# gitarukuranjadi.net
KiCad netlist of a schematic drawn in Altium Designer
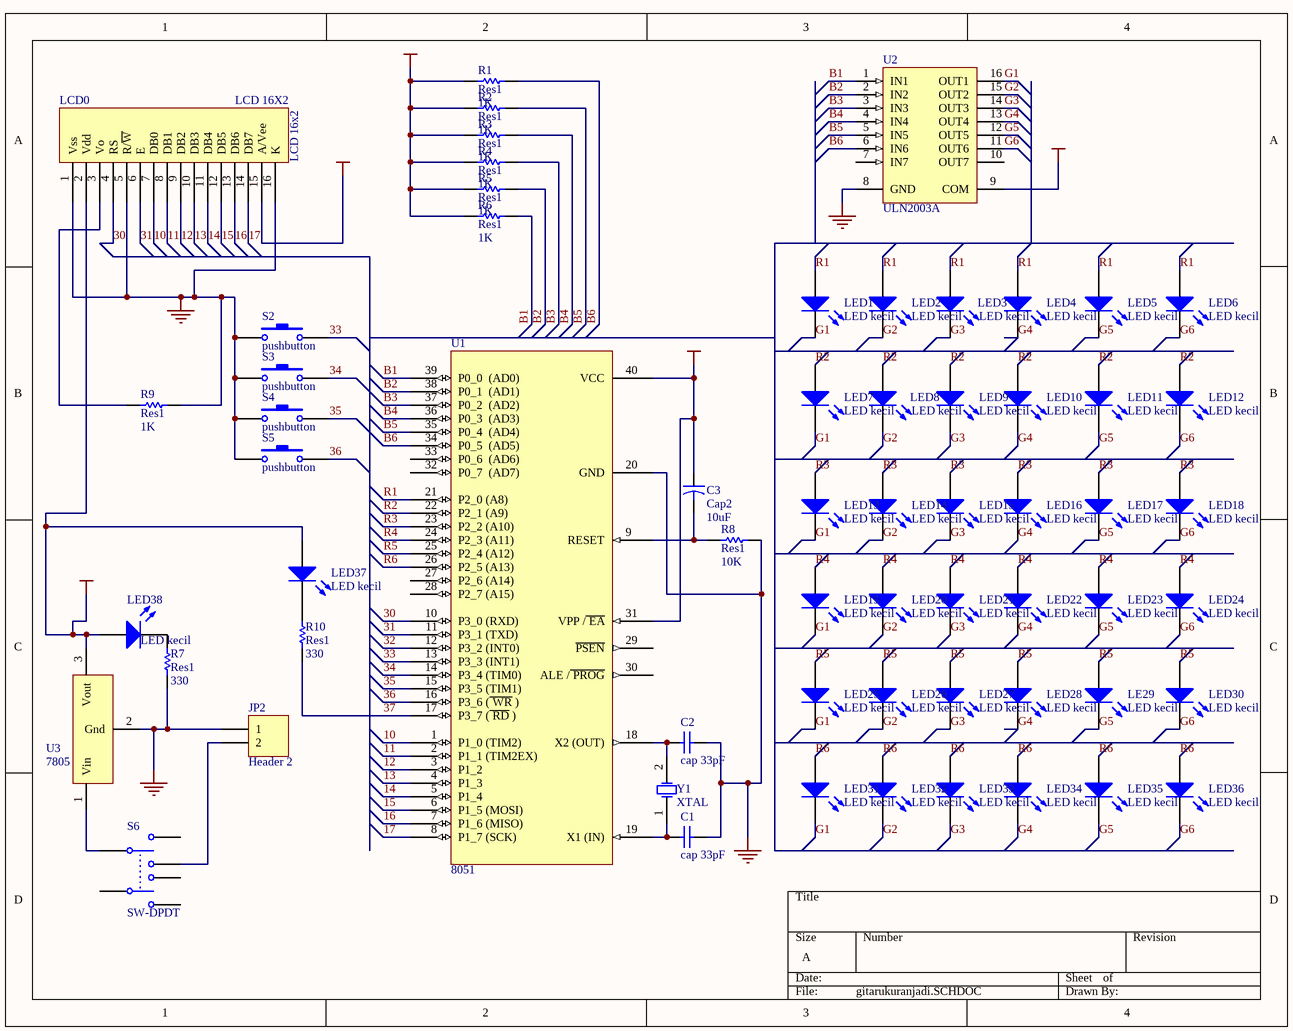
[diagram p0: gitarukuranjadi.SCHDOC]

(export (version "E")
  (design (tool "Eeschema 10.0.6"))
  (components
    (comp (ref "C1")
      (value "cap 33pF")
      (footprint "cap 22/33uF")
      (libsource (lib "agfa other components") (part "cap 22/33uF"))
    )
    (comp (ref "C2")
      (value "cap 33pF")
      (footprint "cap 22/33uF")
      (libsource (lib "agfa other components") (part "cap 22/33uF"))
    )
    (comp (ref "C3")
      (value "Cap2")
      (footprint "CAPR5-4X5")
      (description "Capacitor")
      (fields (field (name "ALTIUM_VALUE") "10uF") (field (name "PUBLISHER") "Altium Limited"))
      (libsource (lib "Miscellaneous Devices") (part "Cap2"))
    )
    (comp (ref "JP2")
      (value "Header 2")
      (footprint "HDR1X2")
      (description "Header, 2-Pin")
      (fields (field (name "PUBLISHER") "Altium Limited"))
      (libsource (lib "Miscellaneous Connectors") (part "Header 2"))
    )
    (comp (ref "LCD0")
      (value "LCD 16X2")
      (footprint "LCD 16X2")
      (libsource (lib "agfa other components") (part "LCD 16X2"))
    )
    (comp (ref "LE29")
      (value "LED kecil")
      (footprint "LED kecil")
      (libsource (lib "agfa other components") (part "LED kecil"))
    )
    (comp (ref "LED1")
      (value "LED kecil")
      (footprint "LED kecil")
      (libsource (lib "agfa other components") (part "LED kecil"))
    )
    (comp (ref "LED2")
      (value "LED kecil")
      (footprint "LED kecil")
      (libsource (lib "agfa other components") (part "LED kecil"))
    )
    (comp (ref "LED3")
      (value "LED kecil")
      (footprint "LED kecil")
      (libsource (lib "agfa other components") (part "LED kecil"))
    )
    (comp (ref "LED4")
      (value "LED kecil")
      (footprint "LED kecil")
      (libsource (lib "agfa other components") (part "LED kecil"))
    )
    (comp (ref "LED5")
      (value "LED kecil")
      (footprint "LED kecil")
      (libsource (lib "agfa other components") (part "LED kecil"))
    )
    (comp (ref "LED6")
      (value "LED kecil")
      (footprint "LED kecil")
      (libsource (lib "agfa other components") (part "LED kecil"))
    )
    (comp (ref "LED7")
      (value "LED kecil")
      (footprint "LED kecil")
      (libsource (lib "agfa other components") (part "LED kecil"))
    )
    (comp (ref "LED8")
      (value "LED kecil")
      (footprint "LED kecil")
      (libsource (lib "agfa other components") (part "LED kecil"))
    )
    (comp (ref "LED9")
      (value "LED kecil")
      (footprint "LED kecil")
      (libsource (lib "agfa other components") (part "LED kecil"))
    )
    (comp (ref "LED10")
      (value "LED kecil")
      (footprint "LED kecil")
      (libsource (lib "agfa other components") (part "LED kecil"))
    )
    (comp (ref "LED11")
      (value "LED kecil")
      (footprint "LED kecil")
      (libsource (lib "agfa other components") (part "LED kecil"))
    )
    (comp (ref "LED12")
      (value "LED kecil")
      (footprint "LED kecil")
      (libsource (lib "agfa other components") (part "LED kecil"))
    )
    (comp (ref "LED13")
      (value "LED kecil")
      (footprint "LED kecil")
      (libsource (lib "agfa other components") (part "LED kecil"))
    )
    (comp (ref "LED14")
      (value "LED kecil")
      (footprint "LED kecil")
      (libsource (lib "agfa other components") (part "LED kecil"))
    )
    (comp (ref "LED15")
      (value "LED kecil")
      (footprint "LED kecil")
      (libsource (lib "agfa other components") (part "LED kecil"))
    )
    (comp (ref "LED16")
      (value "LED kecil")
      (footprint "LED kecil")
      (libsource (lib "agfa other components") (part "LED kecil"))
    )
    (comp (ref "LED17")
      (value "LED kecil")
      (footprint "LED kecil")
      (libsource (lib "agfa other components") (part "LED kecil"))
    )
    (comp (ref "LED18")
      (value "LED kecil")
      (footprint "LED kecil")
      (libsource (lib "agfa other components") (part "LED kecil"))
    )
    (comp (ref "LED19")
      (value "LED kecil")
      (footprint "LED kecil")
      (libsource (lib "agfa other components") (part "LED kecil"))
    )
    (comp (ref "LED20")
      (value "LED kecil")
      (footprint "LED kecil")
      (libsource (lib "agfa other components") (part "LED kecil"))
    )
    (comp (ref "LED21")
      (value "LED kecil")
      (footprint "LED kecil")
      (libsource (lib "agfa other components") (part "LED kecil"))
    )
    (comp (ref "LED22")
      (value "LED kecil")
      (footprint "LED kecil")
      (libsource (lib "agfa other components") (part "LED kecil"))
    )
    (comp (ref "LED23")
      (value "LED kecil")
      (footprint "LED kecil")
      (libsource (lib "agfa other components") (part "LED kecil"))
    )
    (comp (ref "LED24")
      (value "LED kecil")
      (footprint "LED kecil")
      (libsource (lib "agfa other components") (part "LED kecil"))
    )
    (comp (ref "LED25")
      (value "LED kecil")
      (footprint "LED kecil")
      (libsource (lib "agfa other components") (part "LED kecil"))
    )
    (comp (ref "LED26")
      (value "LED kecil")
      (footprint "LED kecil")
      (libsource (lib "agfa other components") (part "LED kecil"))
    )
    (comp (ref "LED27")
      (value "LED kecil")
      (footprint "LED kecil")
      (libsource (lib "agfa other components") (part "LED kecil"))
    )
    (comp (ref "LED28")
      (value "LED kecil")
      (footprint "LED kecil")
      (libsource (lib "agfa other components") (part "LED kecil"))
    )
    (comp (ref "LED30")
      (value "LED kecil")
      (footprint "LED kecil")
      (libsource (lib "agfa other components") (part "LED kecil"))
    )
    (comp (ref "LED31")
      (value "LED kecil")
      (footprint "LED kecil")
      (libsource (lib "agfa other components") (part "LED kecil"))
    )
    (comp (ref "LED32")
      (value "LED kecil")
      (footprint "LED kecil")
      (libsource (lib "agfa other components") (part "LED kecil"))
    )
    (comp (ref "LED33")
      (value "LED kecil")
      (footprint "LED kecil")
      (libsource (lib "agfa other components") (part "LED kecil"))
    )
    (comp (ref "LED34")
      (value "LED kecil")
      (footprint "LED kecil")
      (libsource (lib "agfa other components") (part "LED kecil"))
    )
    (comp (ref "LED35")
      (value "LED kecil")
      (footprint "LED kecil")
      (libsource (lib "agfa other components") (part "LED kecil"))
    )
    (comp (ref "LED36")
      (value "LED kecil")
      (footprint "LED kecil")
      (libsource (lib "agfa other components") (part "LED kecil"))
    )
    (comp (ref "LED37")
      (value "LED kecil")
      (footprint "LED kecil")
      (libsource (lib "agfa other components") (part "LED kecil"))
    )
    (comp (ref "LED38")
      (value "LED kecil")
      (footprint "LED kecil")
      (libsource (lib "agfa other components") (part "LED kecil"))
    )
    (comp (ref "R1")
      (value "Res1")
      (footprint "AXIAL-0.3")
      (description "Resistor")
      (fields (field (name "ALTIUM_VALUE") "1K") (field (name "PUBLISHER") "Altium Limited"))
      (libsource (lib "Miscellaneous Devices") (part "Res1"))
    )
    (comp (ref "R2")
      (value "Res1")
      (footprint "AXIAL-0.3")
      (description "Resistor")
      (fields (field (name "ALTIUM_VALUE") "1K") (field (name "PUBLISHER") "Altium Limited"))
      (libsource (lib "Miscellaneous Devices") (part "Res1"))
    )
    (comp (ref "R3")
      (value "Res1")
      (footprint "AXIAL-0.3")
      (description "Resistor")
      (fields (field (name "ALTIUM_VALUE") "1K") (field (name "PUBLISHER") "Altium Limited"))
      (libsource (lib "Miscellaneous Devices") (part "Res1"))
    )
    (comp (ref "R4")
      (value "Res1")
      (footprint "AXIAL-0.3")
      (description "Resistor")
      (fields (field (name "ALTIUM_VALUE") "1K") (field (name "PUBLISHER") "Altium Limited"))
      (libsource (lib "Miscellaneous Devices") (part "Res1"))
    )
    (comp (ref "R5")
      (value "Res1")
      (footprint "AXIAL-0.3")
      (description "Resistor")
      (fields (field (name "ALTIUM_VALUE") "1K") (field (name "PUBLISHER") "Altium Limited"))
      (libsource (lib "Miscellaneous Devices") (part "Res1"))
    )
    (comp (ref "R6")
      (value "Res1")
      (footprint "AXIAL-0.3")
      (description "Resistor")
      (fields (field (name "ALTIUM_VALUE") "1K") (field (name "PUBLISHER") "Altium Limited"))
      (libsource (lib "Miscellaneous Devices") (part "Res1"))
    )
    (comp (ref "R7")
      (value "Res1")
      (footprint "AXIAL-0.3")
      (description "Resistor")
      (fields (field (name "ALTIUM_VALUE") "330") (field (name "PUBLISHER") "Altium Limited"))
      (libsource (lib "Miscellaneous Devices") (part "Res1"))
    )
    (comp (ref "R8")
      (value "Res1")
      (footprint "AXIAL-0.3")
      (description "Resistor")
      (fields (field (name "ALTIUM_VALUE") "10K") (field (name "PUBLISHER") "Altium Limited"))
      (libsource (lib "Miscellaneous Devices") (part "Res1"))
    )
    (comp (ref "R9")
      (value "Res1")
      (footprint "AXIAL-0.3")
      (description "Resistor")
      (fields (field (name "ALTIUM_VALUE") "1K") (field (name "PUBLISHER") "Altium Limited"))
      (libsource (lib "Miscellaneous Devices") (part "Res1"))
    )
    (comp (ref "R10")
      (value "Res1")
      (footprint "AXIAL-0.3")
      (description "Resistor")
      (fields (field (name "ALTIUM_VALUE") "330") (field (name "PUBLISHER") "Altium Limited"))
      (libsource (lib "Miscellaneous Devices") (part "Res1"))
    )
    (comp (ref "S2")
      (value "pushbutton")
      (footprint "pushbutton")
      (libsource (lib "agfa other components") (part "pushbutton"))
    )
    (comp (ref "S3")
      (value "pushbutton")
      (footprint "pushbutton")
      (libsource (lib "agfa other components") (part "pushbutton"))
    )
    (comp (ref "S4")
      (value "pushbutton")
      (footprint "pushbutton")
      (libsource (lib "agfa other components") (part "pushbutton"))
    )
    (comp (ref "S5")
      (value "pushbutton")
      (footprint "pushbutton")
      (libsource (lib "agfa other components") (part "pushbutton"))
    )
    (comp (ref "S6")
      (value "SW-DPDT")
      (footprint "DPDT-6")
      (description "Double-Pole, Double-Throw Switch")
      (fields (field (name "PUBLISHER") "Altium Limited"))
      (libsource (lib "Miscellaneous Devices") (part "SW-DPDT"))
    )
    (comp (ref "U1")
      (value "8051")
      (footprint "8051 40 pin")
      (libsource (lib "agfa other components") (part "8051 40 pin"))
    )
    (comp (ref "U2")
      (value "ULN2003A")
      (footprint "A16")
      (description "High-Voltage, High-Current Darlington Array")
      (fields (field (name "PUBLISHER") "Altium Limited"))
      (libsource (lib "Allegro Interface Darlington Driver") (part "ULN2003A"))
    )
    (comp (ref "U3")
      (value "7805")
      (footprint "78XX/79XX")
      (libsource (lib "agfa other components") (part "7805/7809/7812/7905/7909/7912"))
    )
    (comp (ref "Y1")
      (value "XTAL")
      (footprint "XTAL")
      (libsource (lib "agfa other components") (part "XTAL"))
    )
  )
  (nets
    (net (code "1") (name "/10") (class "Default")
      (node (ref "LCD0") (pin "7") (pinfunction "DB0_7") (pintype "passive"))
      (node (ref "U1") (pin "1") (pinfunction "P1_0_(TIM2)_1") (pintype "bidirectional"))
    )
    (net (code "2") (name "/11") (class "Default")
      (node (ref "LCD0") (pin "8") (pinfunction "DB1_8") (pintype "passive"))
      (node (ref "U1") (pin "2") (pinfunction "P1_1_(TIM2EX)_2") (pintype "bidirectional"))
    )
    (net (code "3") (name "/12") (class "Default")
      (node (ref "LCD0") (pin "9") (pinfunction "DB2_9") (pintype "passive"))
      (node (ref "U1") (pin "3") (pinfunction "P1_2_3") (pintype "bidirectional"))
    )
    (net (code "4") (name "/13") (class "Default")
      (node (ref "LCD0") (pin "10") (pinfunction "DB3_10") (pintype "passive"))
      (node (ref "U1") (pin "4") (pinfunction "P1_3_4") (pintype "bidirectional"))
    )
    (net (code "5") (name "/14") (class "Default")
      (node (ref "LCD0") (pin "11") (pinfunction "DB4_11") (pintype "passive"))
      (node (ref "U1") (pin "5") (pinfunction "P1_4_5") (pintype "bidirectional"))
    )
    (net (code "6") (name "/15") (class "Default")
      (node (ref "LCD0") (pin "12") (pinfunction "DB5_12") (pintype "passive"))
      (node (ref "U1") (pin "6") (pinfunction "P1_5_(MOSI)_6") (pintype "bidirectional"))
    )
    (net (code "7") (name "/16") (class "Default")
      (node (ref "LCD0") (pin "13") (pinfunction "DB6_13") (pintype "passive"))
      (node (ref "U1") (pin "7") (pinfunction "P1_6_(MISO)_7") (pintype "bidirectional"))
    )
    (net (code "8") (name "/17") (class "Default")
      (node (ref "LCD0") (pin "14") (pinfunction "DB7_14") (pintype "passive"))
      (node (ref "U1") (pin "8") (pinfunction "P1_7_(SCK)_8") (pintype "bidirectional"))
    )
    (net (code "9") (name "/30") (class "Default")
      (node (ref "LCD0") (pin "4") (pinfunction "RS_4") (pintype "passive"))
      (node (ref "U1") (pin "10") (pinfunction "P3_0_(RXD)_10") (pintype "bidirectional"))
    )
    (net (code "10") (name "/31") (class "Default")
      (node (ref "LCD0") (pin "6") (pinfunction "E_6") (pintype "passive"))
      (node (ref "U1") (pin "11") (pinfunction "P3_1_(TXD)_11") (pintype "bidirectional"))
    )
    (net (code "11") (name "/32") (class "Default")
      (node (ref "U1") (pin "12") (pinfunction "P3_2_(INT0)_12") (pintype "bidirectional"))
    )
    (net (code "12") (name "/33") (class "Default")
      (node (ref "S2") (pin "2") (pinfunction "2_2") (pintype "passive"))
      (node (ref "U1") (pin "13") (pinfunction "P3_3_(INT1)_13") (pintype "bidirectional"))
    )
    (net (code "13") (name "/34") (class "Default")
      (node (ref "S3") (pin "2") (pinfunction "2_2") (pintype "passive"))
      (node (ref "U1") (pin "14") (pinfunction "P3_4_(TIM0)_14") (pintype "bidirectional"))
    )
    (net (code "14") (name "/35") (class "Default")
      (node (ref "S4") (pin "2") (pinfunction "2_2") (pintype "passive"))
      (node (ref "U1") (pin "15") (pinfunction "P3_5_(TIM1)_15") (pintype "bidirectional"))
    )
    (net (code "15") (name "/36") (class "Default")
      (node (ref "S5") (pin "2") (pinfunction "2_2") (pintype "passive"))
      (node (ref "U1") (pin "16") (pinfunction "P3_6_(~{_WR}_)_16") (pintype "bidirectional"))
    )
    (net (code "16") (name "/37") (class "Default")
      (node (ref "R10") (pin "1") (pinfunction "1_1") (pintype "passive"))
      (node (ref "U1") (pin "17") (pinfunction "P3_7_(~{_RD}_)_17") (pintype "bidirectional"))
    )
    (net (code "17") (name "/B1") (class "Default")
      (node (ref "R6") (pin "2") (pinfunction "2_2") (pintype "passive"))
      (node (ref "U1") (pin "39") (pinfunction "P0_0__(AD0)_39") (pintype "bidirectional"))
      (node (ref "U2") (pin "1") (pinfunction "IN1_1") (pintype "input"))
    )
    (net (code "18") (name "/B2") (class "Default")
      (node (ref "R5") (pin "2") (pinfunction "2_2") (pintype "passive"))
      (node (ref "U1") (pin "38") (pinfunction "P0_1__(AD1)_38") (pintype "bidirectional"))
      (node (ref "U2") (pin "2") (pinfunction "IN2_2") (pintype "input"))
    )
    (net (code "19") (name "/B3") (class "Default")
      (node (ref "R4") (pin "2") (pinfunction "2_2") (pintype "passive"))
      (node (ref "U1") (pin "37") (pinfunction "P0_2__(AD2)_37") (pintype "bidirectional"))
      (node (ref "U2") (pin "3") (pinfunction "IN3_3") (pintype "input"))
    )
    (net (code "20") (name "/B4") (class "Default")
      (node (ref "R3") (pin "2") (pinfunction "2_2") (pintype "passive"))
      (node (ref "U1") (pin "36") (pinfunction "P0_3__(AD3)_36") (pintype "bidirectional"))
      (node (ref "U2") (pin "4") (pinfunction "IN4_4") (pintype "input"))
    )
    (net (code "21") (name "/B5") (class "Default")
      (node (ref "R2") (pin "2") (pinfunction "2_2") (pintype "passive"))
      (node (ref "U1") (pin "35") (pinfunction "P0_4__(AD4)_35") (pintype "bidirectional"))
      (node (ref "U2") (pin "5") (pinfunction "IN5_5") (pintype "input"))
    )
    (net (code "22") (name "/B6") (class "Default")
      (node (ref "R1") (pin "2") (pinfunction "2_2") (pintype "passive"))
      (node (ref "U1") (pin "34") (pinfunction "P0_5__(AD5)_34") (pintype "bidirectional"))
      (node (ref "U2") (pin "6") (pinfunction "IN6_6") (pintype "input"))
    )
    (net (code "23") (name "/G1") (class "Default")
      (node (ref "LED1") (pin "2") (pinfunction "K_2") (pintype "passive"))
      (node (ref "LED13") (pin "2") (pinfunction "K_2") (pintype "passive"))
      (node (ref "LED19") (pin "2") (pinfunction "K_2") (pintype "passive"))
      (node (ref "LED25") (pin "2") (pinfunction "K_2") (pintype "passive"))
      (node (ref "LED31") (pin "2") (pinfunction "K_2") (pintype "passive"))
      (node (ref "LED7") (pin "2") (pinfunction "K_2") (pintype "passive"))
      (node (ref "U2") (pin "16") (pinfunction "OUT1_16") (pintype "open_collector"))
    )
    (net (code "24") (name "/G2") (class "Default")
      (node (ref "LED14") (pin "2") (pinfunction "K_2") (pintype "passive"))
      (node (ref "LED2") (pin "2") (pinfunction "K_2") (pintype "passive"))
      (node (ref "LED20") (pin "2") (pinfunction "K_2") (pintype "passive"))
      (node (ref "LED26") (pin "2") (pinfunction "K_2") (pintype "passive"))
      (node (ref "LED32") (pin "2") (pinfunction "K_2") (pintype "passive"))
      (node (ref "LED8") (pin "2") (pinfunction "K_2") (pintype "passive"))
      (node (ref "U2") (pin "15") (pinfunction "OUT2_15") (pintype "open_collector"))
    )
    (net (code "25") (name "/G3") (class "Default")
      (node (ref "LED15") (pin "2") (pinfunction "K_2") (pintype "passive"))
      (node (ref "LED21") (pin "2") (pinfunction "K_2") (pintype "passive"))
      (node (ref "LED27") (pin "2") (pinfunction "K_2") (pintype "passive"))
      (node (ref "LED3") (pin "2") (pinfunction "K_2") (pintype "passive"))
      (node (ref "LED33") (pin "2") (pinfunction "K_2") (pintype "passive"))
      (node (ref "LED9") (pin "2") (pinfunction "K_2") (pintype "passive"))
      (node (ref "U2") (pin "14") (pinfunction "OUT3_14") (pintype "open_collector"))
    )
    (net (code "26") (name "/G4") (class "Default")
      (node (ref "LED10") (pin "2") (pinfunction "K_2") (pintype "passive"))
      (node (ref "LED16") (pin "2") (pinfunction "K_2") (pintype "passive"))
      (node (ref "LED22") (pin "2") (pinfunction "K_2") (pintype "passive"))
      (node (ref "LED28") (pin "2") (pinfunction "K_2") (pintype "passive"))
      (node (ref "LED34") (pin "2") (pinfunction "K_2") (pintype "passive"))
      (node (ref "LED4") (pin "2") (pinfunction "K_2") (pintype "passive"))
      (node (ref "U2") (pin "13") (pinfunction "OUT4_13") (pintype "open_collector"))
    )
    (net (code "27") (name "/G5") (class "Default")
      (node (ref "LE29") (pin "2") (pinfunction "K_2") (pintype "passive"))
      (node (ref "LED11") (pin "2") (pinfunction "K_2") (pintype "passive"))
      (node (ref "LED17") (pin "2") (pinfunction "K_2") (pintype "passive"))
      (node (ref "LED23") (pin "2") (pinfunction "K_2") (pintype "passive"))
      (node (ref "LED35") (pin "2") (pinfunction "K_2") (pintype "passive"))
      (node (ref "LED5") (pin "2") (pinfunction "K_2") (pintype "passive"))
      (node (ref "U2") (pin "12") (pinfunction "OUT5_12") (pintype "open_collector"))
    )
    (net (code "28") (name "/G6") (class "Default")
      (node (ref "LED12") (pin "2") (pinfunction "K_2") (pintype "passive"))
      (node (ref "LED18") (pin "2") (pinfunction "K_2") (pintype "passive"))
      (node (ref "LED24") (pin "2") (pinfunction "K_2") (pintype "passive"))
      (node (ref "LED30") (pin "2") (pinfunction "K_2") (pintype "passive"))
      (node (ref "LED36") (pin "2") (pinfunction "K_2") (pintype "passive"))
      (node (ref "LED6") (pin "2") (pinfunction "K_2") (pintype "passive"))
      (node (ref "U2") (pin "11") (pinfunction "OUT6_11") (pintype "open_collector"))
    )
    (net (code "29") (name "/R1") (class "Default")
      (node (ref "LED1") (pin "1") (pinfunction "A_1") (pintype "passive"))
      (node (ref "LED2") (pin "1") (pinfunction "A_1") (pintype "passive"))
      (node (ref "LED3") (pin "1") (pinfunction "A_1") (pintype "passive"))
      (node (ref "LED4") (pin "1") (pinfunction "A_1") (pintype "passive"))
      (node (ref "LED5") (pin "1") (pinfunction "A_1") (pintype "passive"))
      (node (ref "LED6") (pin "1") (pinfunction "A_1") (pintype "passive"))
      (node (ref "U1") (pin "21") (pinfunction "P2_0_(A8)_21") (pintype "bidirectional"))
    )
    (net (code "30") (name "/R2") (class "Default")
      (node (ref "LED10") (pin "1") (pinfunction "A_1") (pintype "passive"))
      (node (ref "LED11") (pin "1") (pinfunction "A_1") (pintype "passive"))
      (node (ref "LED12") (pin "1") (pinfunction "A_1") (pintype "passive"))
      (node (ref "LED7") (pin "1") (pinfunction "A_1") (pintype "passive"))
      (node (ref "LED8") (pin "1") (pinfunction "A_1") (pintype "passive"))
      (node (ref "LED9") (pin "1") (pinfunction "A_1") (pintype "passive"))
      (node (ref "U1") (pin "22") (pinfunction "P2_1_(A9)_22") (pintype "bidirectional"))
    )
    (net (code "31") (name "/R3") (class "Default")
      (node (ref "LED13") (pin "1") (pinfunction "A_1") (pintype "passive"))
      (node (ref "LED14") (pin "1") (pinfunction "A_1") (pintype "passive"))
      (node (ref "LED15") (pin "1") (pinfunction "A_1") (pintype "passive"))
      (node (ref "LED16") (pin "1") (pinfunction "A_1") (pintype "passive"))
      (node (ref "LED17") (pin "1") (pinfunction "A_1") (pintype "passive"))
      (node (ref "LED18") (pin "1") (pinfunction "A_1") (pintype "passive"))
      (node (ref "U1") (pin "23") (pinfunction "P2_2_(A10)_23") (pintype "bidirectional"))
    )
    (net (code "32") (name "/R4") (class "Default")
      (node (ref "LED19") (pin "1") (pinfunction "A_1") (pintype "passive"))
      (node (ref "LED20") (pin "1") (pinfunction "A_1") (pintype "passive"))
      (node (ref "LED21") (pin "1") (pinfunction "A_1") (pintype "passive"))
      (node (ref "LED22") (pin "1") (pinfunction "A_1") (pintype "passive"))
      (node (ref "LED23") (pin "1") (pinfunction "A_1") (pintype "passive"))
      (node (ref "LED24") (pin "1") (pinfunction "A_1") (pintype "passive"))
      (node (ref "U1") (pin "24") (pinfunction "P2_3_(A11)_24") (pintype "bidirectional"))
    )
    (net (code "33") (name "/R5") (class "Default")
      (node (ref "LE29") (pin "1") (pinfunction "A_1") (pintype "passive"))
      (node (ref "LED25") (pin "1") (pinfunction "A_1") (pintype "passive"))
      (node (ref "LED26") (pin "1") (pinfunction "A_1") (pintype "passive"))
      (node (ref "LED27") (pin "1") (pinfunction "A_1") (pintype "passive"))
      (node (ref "LED28") (pin "1") (pinfunction "A_1") (pintype "passive"))
      (node (ref "LED30") (pin "1") (pinfunction "A_1") (pintype "passive"))
      (node (ref "U1") (pin "25") (pinfunction "P2_4_(A12)_25") (pintype "bidirectional"))
    )
    (net (code "34") (name "/R6") (class "Default")
      (node (ref "LED31") (pin "1") (pinfunction "A_1") (pintype "passive"))
      (node (ref "LED32") (pin "1") (pinfunction "A_1") (pintype "passive"))
      (node (ref "LED33") (pin "1") (pinfunction "A_1") (pintype "passive"))
      (node (ref "LED34") (pin "1") (pinfunction "A_1") (pintype "passive"))
      (node (ref "LED35") (pin "1") (pinfunction "A_1") (pintype "passive"))
      (node (ref "LED36") (pin "1") (pinfunction "A_1") (pintype "passive"))
      (node (ref "U1") (pin "26") (pinfunction "P2_5_(A13)_26") (pintype "bidirectional"))
    )
    (net (code "35") (name "GND") (class "Default")
      (node (ref "C1") (pin "2") (pinfunction "2_2") (pintype "passive"))
      (node (ref "C2") (pin "2") (pinfunction "2_2") (pintype "passive"))
      (node (ref "JP2") (pin "1") (pinfunction "1_1") (pintype "passive"))
      (node (ref "LCD0") (pin "1") (pinfunction "Vss_1") (pintype "passive"))
      (node (ref "LCD0") (pin "16") (pinfunction "K_16") (pintype "passive"))
      (node (ref "LCD0") (pin "5") (pinfunction "R/~{W}_5") (pintype "passive"))
      (node (ref "R7") (pin "1") (pinfunction "1_1") (pintype "passive"))
      (node (ref "R8") (pin "2") (pinfunction "2_2") (pintype "passive"))
      (node (ref "R9") (pin "2") (pinfunction "2_2") (pintype "passive"))
      (node (ref "S2") (pin "1") (pinfunction "1_1") (pintype "passive"))
      (node (ref "S3") (pin "1") (pinfunction "1_1") (pintype "passive"))
      (node (ref "S4") (pin "1") (pinfunction "1_1") (pintype "passive"))
      (node (ref "S5") (pin "1") (pinfunction "1_1") (pintype "passive"))
      (node (ref "U1") (pin "20") (pinfunction "GND_20") (pintype "power_in"))
      (node (ref "U2") (pin "8") (pinfunction "GND_8") (pintype "power_in"))
      (node (ref "U3") (pin "2") (pinfunction "Gnd_2") (pintype "passive"))
    )
    (net (code "36") (name "Net-(JP2-Pad2)") (class "Default")
      (node (ref "JP2") (pin "2") (pinfunction "2_2") (pintype "passive"))
      (node (ref "S6") (pin "3") (pinfunction "3_3") (pintype "passive"))
    )
    (net (code "37") (name "Net-(LCD0-Vo)") (class "Default")
      (node (ref "LCD0") (pin "3") (pinfunction "Vo_3") (pintype "passive"))
      (node (ref "R9") (pin "1") (pinfunction "1_1") (pintype "passive"))
    )
    (net (code "38") (name "Net-(LED37-K)") (class "Default")
      (node (ref "LED37") (pin "2") (pinfunction "K_2") (pintype "passive"))
      (node (ref "R10") (pin "2") (pinfunction "2_2") (pintype "passive"))
    )
    (net (code "39") (name "Net-(LED38-K)") (class "Default")
      (node (ref "LED38") (pin "2") (pinfunction "K_2") (pintype "passive"))
      (node (ref "R7") (pin "2") (pinfunction "2_2") (pintype "passive"))
    )
    (net (code "40") (name "Net-(U1-RESET)") (class "Default")
      (node (ref "C3") (pin "2") (pinfunction "2_2") (pintype "passive"))
      (node (ref "R8") (pin "1") (pinfunction "1_1") (pintype "passive"))
      (node (ref "U1") (pin "9") (pinfunction "RESET_9") (pintype "input"))
    )
    (net (code "41") (name "Net-(U1-X1_(IN))") (class "Default")
      (node (ref "C1") (pin "1") (pinfunction "1_1") (pintype "passive"))
      (node (ref "U1") (pin "19") (pinfunction "X1_(IN)_19") (pintype "input"))
      (node (ref "Y1") (pin "1") (pinfunction "OSC1_1") (pintype "passive"))
    )
    (net (code "42") (name "Net-(U1-X2_(OUT))") (class "Default")
      (node (ref "C2") (pin "1") (pinfunction "1_1") (pintype "passive"))
      (node (ref "U1") (pin "18") (pinfunction "X2_(OUT)_18") (pintype "output"))
      (node (ref "Y1") (pin "2") (pinfunction "OSC2_2") (pintype "passive"))
    )
    (net (code "43") (name "Net-(U3-Vin)") (class "Default")
      (node (ref "S6") (pin "1") (pinfunction "1_1") (pintype "passive"))
      (node (ref "U3") (pin "1") (pinfunction "Vin_1") (pintype "passive"))
    )
    (net (code "44") (name "VCC") (class "Default")
      (node (ref "C3") (pin "1") (pinfunction "1_1") (pintype "passive"))
      (node (ref "LCD0") (pin "15") (pinfunction "A/Vee_15") (pintype "passive"))
      (node (ref "LCD0") (pin "2") (pinfunction "Vdd_2") (pintype "passive"))
      (node (ref "LED37") (pin "1") (pinfunction "A_1") (pintype "passive"))
      (node (ref "LED38") (pin "1") (pinfunction "A_1") (pintype "passive"))
      (node (ref "R1") (pin "1") (pinfunction "1_1") (pintype "passive"))
      (node (ref "R2") (pin "1") (pinfunction "1_1") (pintype "passive"))
      (node (ref "R3") (pin "1") (pinfunction "1_1") (pintype "passive"))
      (node (ref "R4") (pin "1") (pinfunction "1_1") (pintype "passive"))
      (node (ref "R5") (pin "1") (pinfunction "1_1") (pintype "passive"))
      (node (ref "R6") (pin "1") (pinfunction "1_1") (pintype "passive"))
      (node (ref "U1") (pin "31") (pinfunction "VPP_/~{_EA}_31") (pintype "input"))
      (node (ref "U1") (pin "40") (pinfunction "VCC_40") (pintype "power_in"))
      (node (ref "U2") (pin "9") (pinfunction "COM_9") (pintype "passive"))
      (node (ref "U3") (pin "3") (pinfunction "Vout_3") (pintype "passive"))
    )
    (net (code "45") (name "unconnected-(S6-Pad2)") (class "Default")
      (node (ref "S6") (pin "2") (pinfunction "2_2") (pintype "passive"))
    )
    (net (code "46") (name "unconnected-(S6-Pad4)") (class "Default")
      (node (ref "S6") (pin "4") (pinfunction "4_4") (pintype "passive"))
    )
    (net (code "47") (name "unconnected-(S6-Pad5)") (class "Default")
      (node (ref "S6") (pin "5") (pinfunction "5_5") (pintype "passive"))
    )
    (net (code "48") (name "unconnected-(S6-Pad6)") (class "Default")
      (node (ref "S6") (pin "6") (pinfunction "6_6") (pintype "passive"))
    )
    (net (code "49") (name "unconnected-(U1-ALE_{slash}~{_PROG}-Pad30)") (class "Default")
      (node (ref "U1") (pin "30") (pinfunction "ALE_/~{_PROG}_30") (pintype "output"))
    )
    (net (code "50") (name "unconnected-(U1-P0_6__(AD6)-Pad33)") (class "Default")
      (node (ref "U1") (pin "33") (pinfunction "P0_6__(AD6)_33") (pintype "bidirectional"))
    )
    (net (code "51") (name "unconnected-(U1-P0_7__(AD7)-Pad32)") (class "Default")
      (node (ref "U1") (pin "32") (pinfunction "P0_7__(AD7)_32") (pintype "bidirectional"))
    )
    (net (code "52") (name "unconnected-(U1-P2_6_(A14)-Pad27)") (class "Default")
      (node (ref "U1") (pin "27") (pinfunction "P2_6_(A14)_27") (pintype "bidirectional"))
    )
    (net (code "53") (name "unconnected-(U1-P2_7_(A15)-Pad28)") (class "Default")
      (node (ref "U1") (pin "28") (pinfunction "P2_7_(A15)_28") (pintype "bidirectional"))
    )
    (net (code "54") (name "unconnected-(U1-PSEN-Pad29)") (class "Default")
      (node (ref "U1") (pin "29") (pinfunction "PSEN_29") (pintype "output"))
    )
    (net (code "55") (name "unconnected-(U2-IN7-Pad7)") (class "Default")
      (node (ref "U2") (pin "7") (pinfunction "IN7_7") (pintype "input"))
    )
    (net (code "56") (name "unconnected-(U2-OUT7-Pad10)") (class "Default")
      (node (ref "U2") (pin "10") (pinfunction "OUT7_10") (pintype "open_collector"))
    )
  )
)
